# SCH_CHAITANYANFC_2024-05-23.net
KiCad netlist of a schematic drawn in EasyEDA
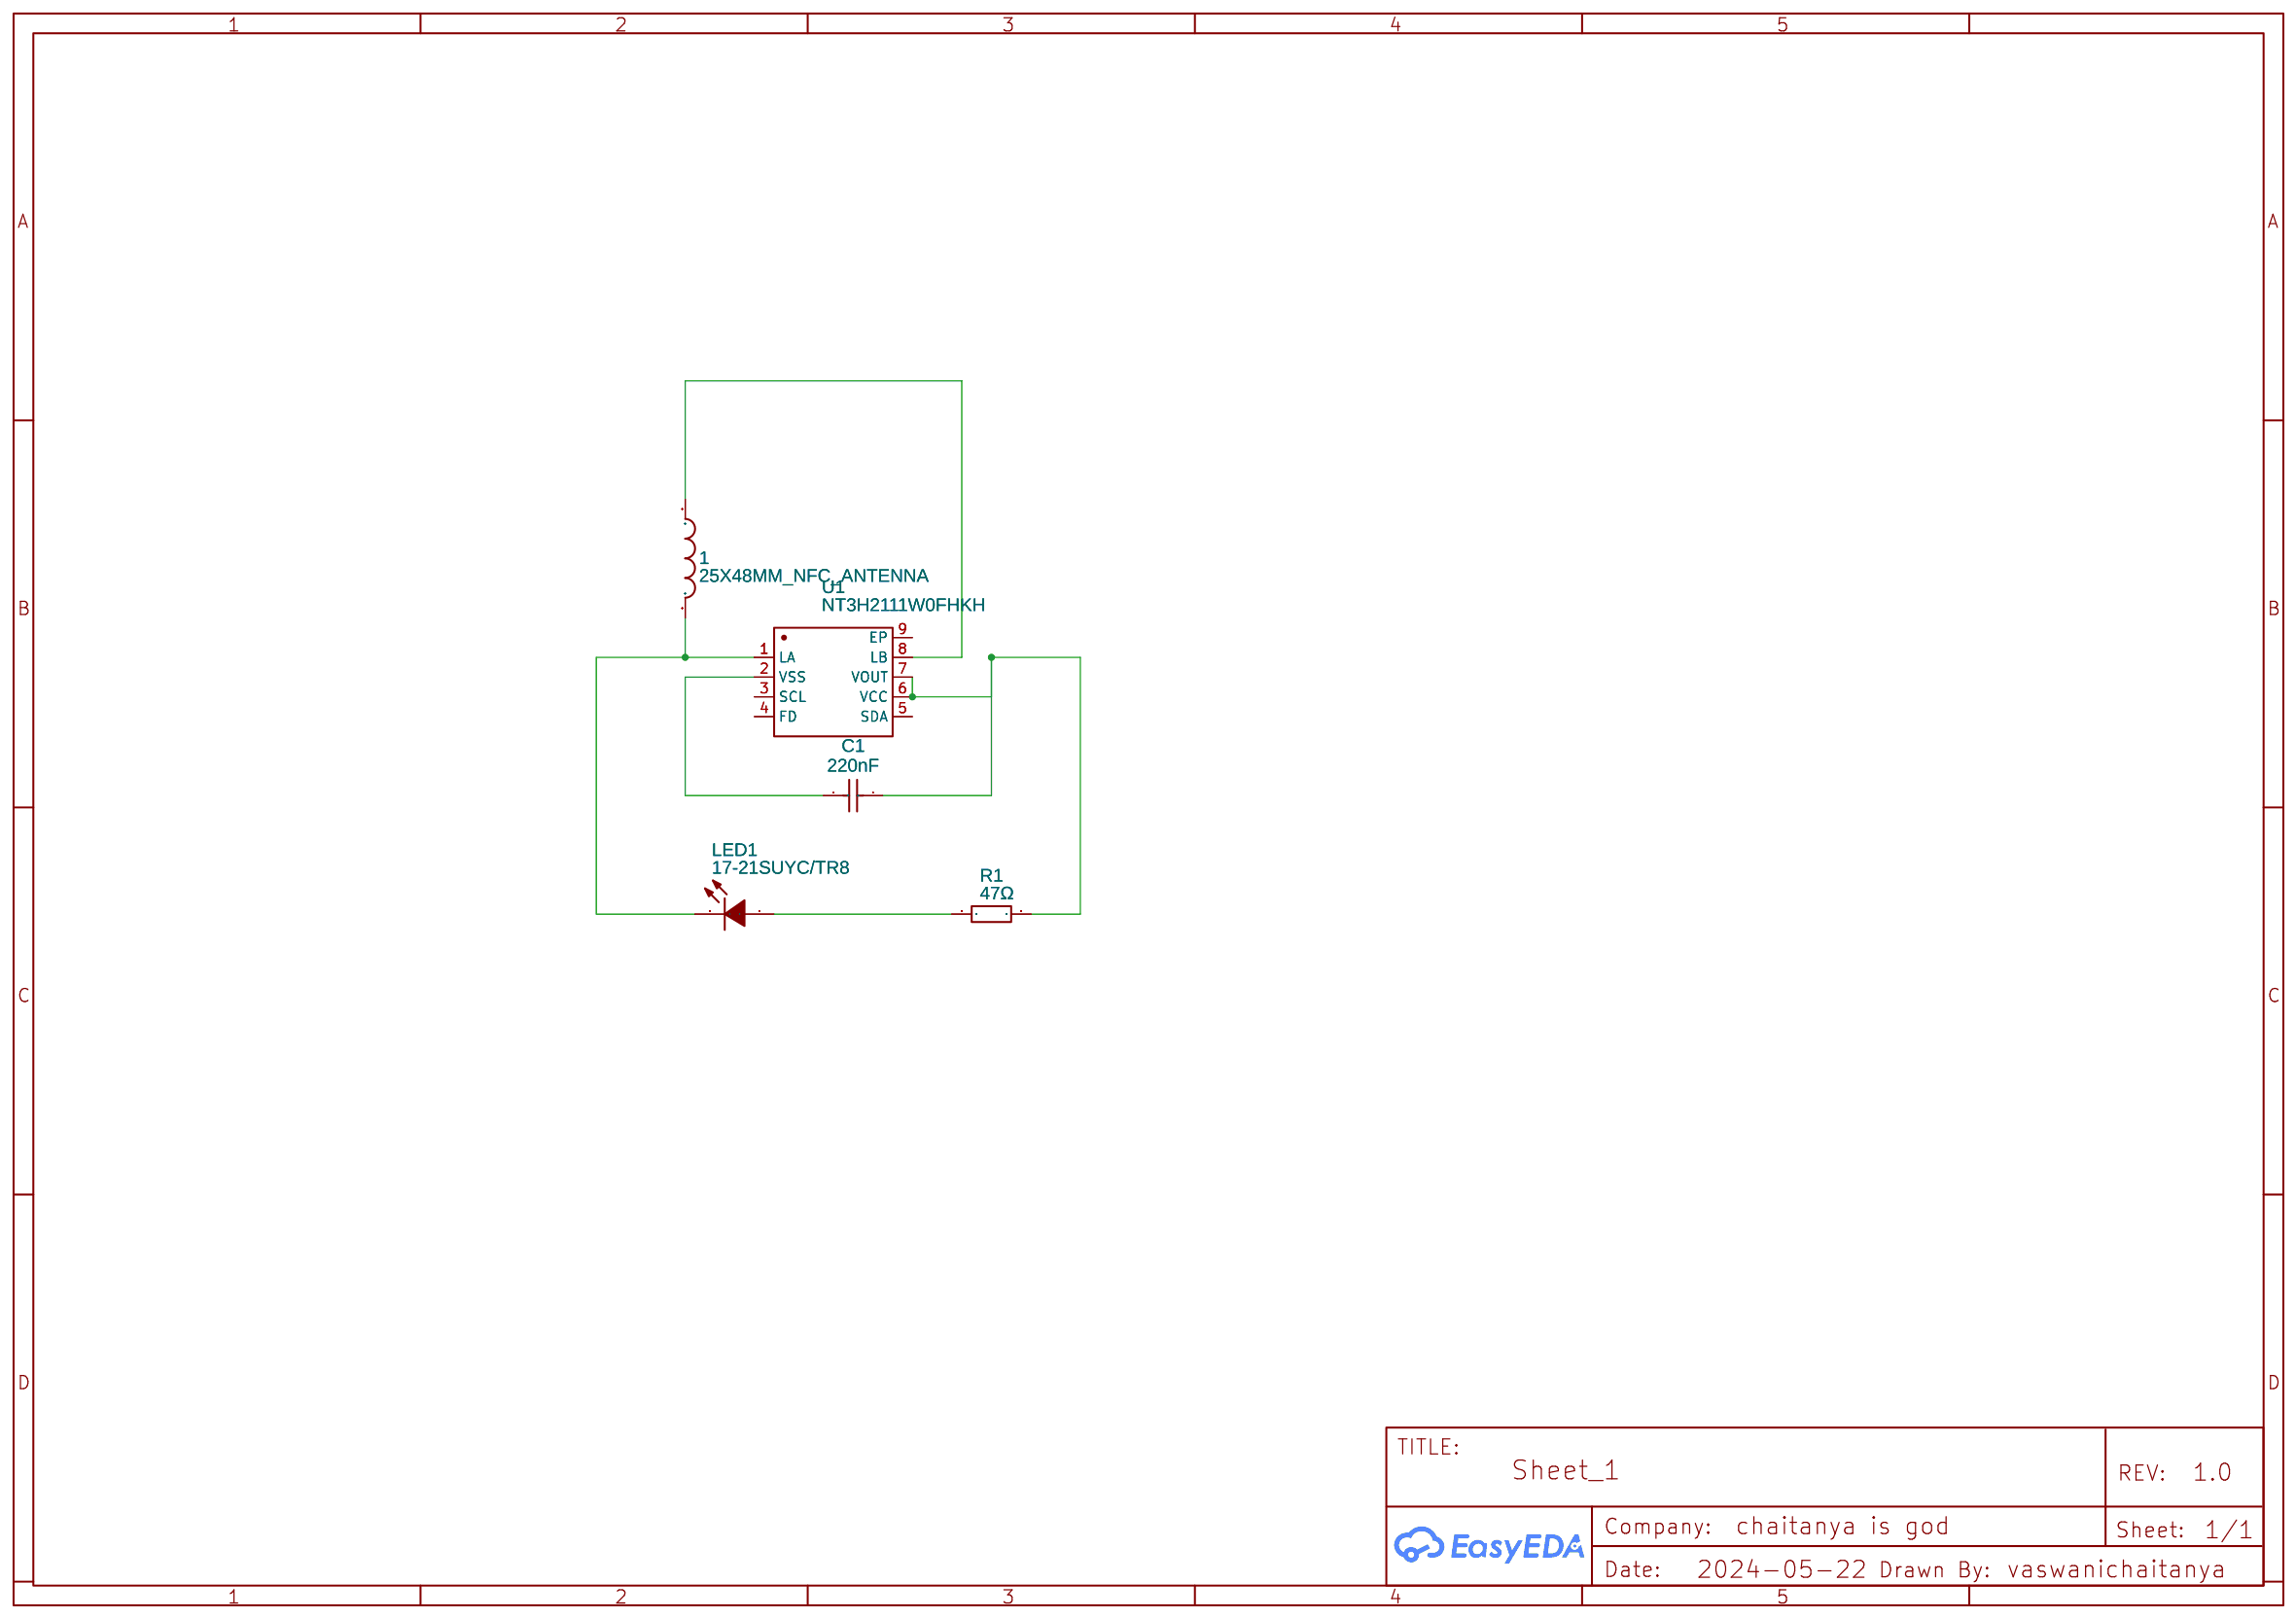
[diagram p0: schematic sheet]

(export (version "E")
  (design (tool "Eeschema 10.0.6"))
  (components
    (comp (ref "1") (value "25X48MM_NFC_ANTENNA") (libsource (lib "") (part "25X48MM_NFC_ANTENNA")))
    (comp (ref "C1")
      (value "220nF")
      (fields (field (name "Manufacturer Part") "CL10B224KA8NNNC") (field (name "Manufacturer") "SAMSUNG"))
      (libsource (lib "") (part "220N CL10B224KA8NNNC"))
    )
    (comp (ref "LED1")
      (value "17-21SUYC/TR8")
      (fields (field (name "Manufacturer Part") "KT-0805黄灯") (field (name "Manufacturer") "KENTO"))
      (libsource (lib "") (part "17-21SUYC/TR8"))
    )
    (comp (ref "R1")
      (value "47Ω")
      (fields
        (field (name "Manufacturer Part") "0603WAF470JT5E")
        (field (name "Manufacturer") "UNI-ROYAL(厚声)")
      )
      (libsource (lib "") (part "0603WAF470JT5E"))
    )
    (comp (ref "U1")
      (value "NT3H2111W0FHKH")
      (fields (field (name "Manufacturer") "NXP(恩智浦)"))
      (libsource (lib "") (part "NT3H2111W0FHKH"))
    )
  )
  (nets
    (net (code "1") (name "Net-(LED1-+)") (class "Default")
      (node (ref "LED1") (pin "1") (pinfunction "+_1") (pintype "unspecified"))
      (node (ref "R1") (pin "1") (pinfunction "1_1") (pintype "input"))
    )
    (net (code "2") (name "Net-(LED1--)") (class "Default")
      (node (ref "1") (pin "P$2") (pinfunction "P$2_P$2") (pintype "bidirectional"))
      (node (ref "LED1") (pin "2") (pinfunction "-_2") (pintype "unspecified"))
      (node (ref "U1") (pin "1") (pinfunction "LA_1") (pintype "unspecified"))
    )
    (net (code "3") (name "Net-(U1-LB)") (class "Default")
      (node (ref "1") (pin "P$1") (pinfunction "P$1_P$1") (pintype "bidirectional"))
      (node (ref "U1") (pin "8") (pinfunction "LB_8") (pintype "unspecified"))
    )
    (net (code "4") (name "Net-(U1-VCC)") (class "Default")
      (node (ref "C1") (pin "2") (pinfunction "2_2") (pintype "input"))
      (node (ref "R1") (pin "2") (pinfunction "2_2") (pintype "input"))
      (node (ref "U1") (pin "6") (pinfunction "VCC_6") (pintype "unspecified"))
      (node (ref "U1") (pin "7") (pinfunction "VOUT_7") (pintype "unspecified"))
    )
    (net (code "5") (name "Net-(U1-VSS)") (class "Default")
      (node (ref "C1") (pin "1") (pinfunction "1_1") (pintype "input"))
      (node (ref "U1") (pin "2") (pinfunction "VSS_2") (pintype "unspecified"))
    )
    (net (code "6") (name "unconnected-(U1-EP-Pad9)") (class "Default")
      (node (ref "U1") (pin "9") (pinfunction "EP_9") (pintype "unspecified"))
    )
    (net (code "7") (name "unconnected-(U1-FD-Pad4)") (class "Default")
      (node (ref "U1") (pin "4") (pinfunction "FD_4") (pintype "unspecified"))
    )
    (net (code "8") (name "unconnected-(U1-SCL-Pad3)") (class "Default")
      (node (ref "U1") (pin "3") (pinfunction "SCL_3") (pintype "unspecified"))
    )
    (net (code "9") (name "unconnected-(U1-SDA-Pad5)") (class "Default")
      (node (ref "U1") (pin "5") (pinfunction "SDA_5") (pintype "unspecified"))
    )
  )
)
